# MRCS-4-Station-Tel-Control.net
KiCad netlist of a schematic drawn in EAGLE
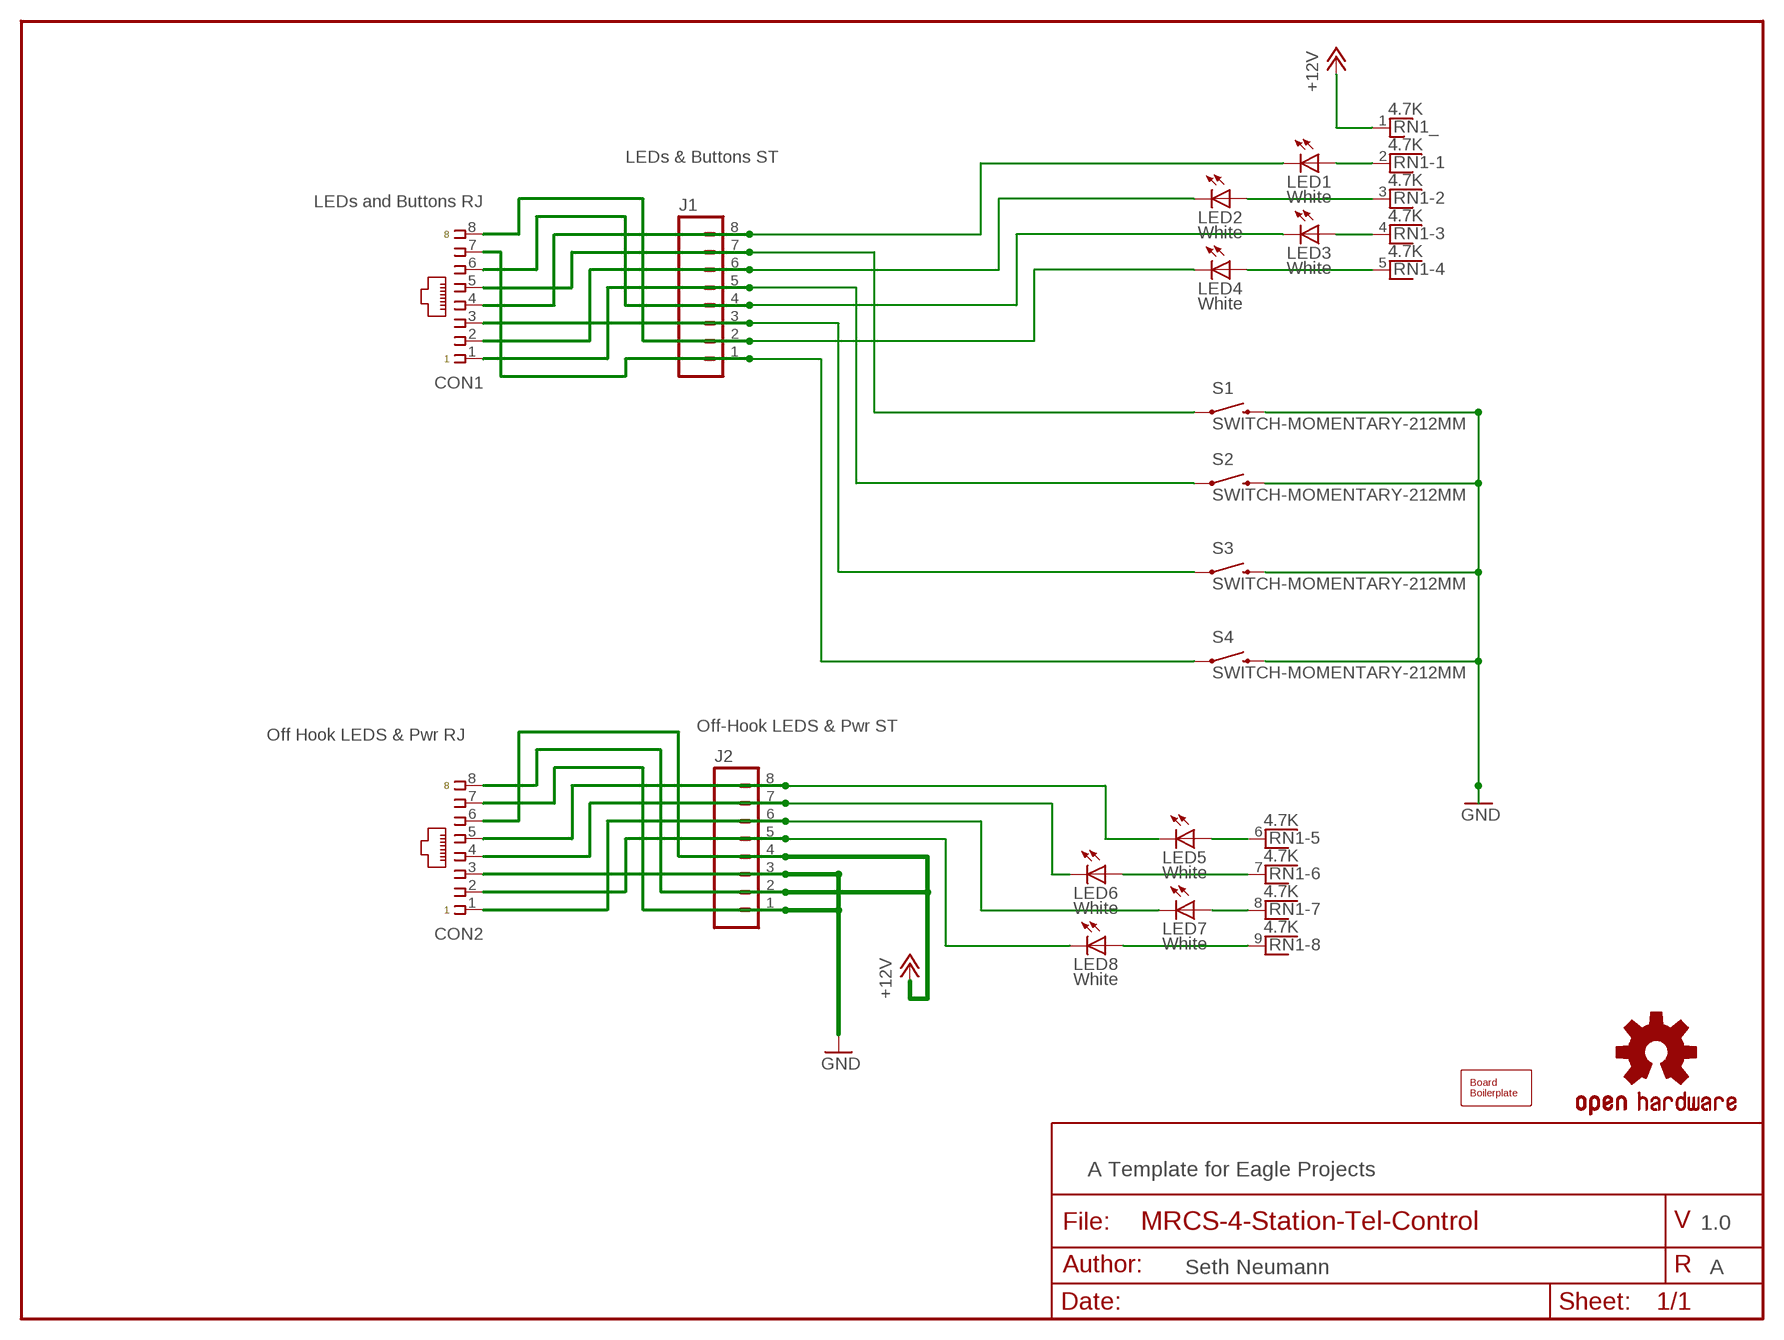
[diagram p0: schematic, sheet 1]

(export (version "E")
  (design (tool "Eeschema 10.0.6"))
  (components
    (comp (ref "BOARD1")
      (value "BOARD80X100")
      (footprint "eagle-import:BOARD-DINRAIL-3.17INX10CM")
      (libsource (lib "eagle-import") (part "BOARD80X100"))
    )
    (comp (ref "CON1")
      (value "LEDs and Buttons RJ")
      (footprint "eagle-import:RJ45-NO-SHIELD")
      (libsource (lib "eagle-import") (part "CONNECTOR-RJ45-FRONT"))
    )
    (comp (ref "CON2")
      (value "Off Hook LEDS & Pwr RJ")
      (footprint "eagle-import:RJ45-NO-SHIELD")
      (libsource (lib "eagle-import") (part "CONNECTOR-RJ45-FRONT"))
    )
    (comp (ref "J1")
      (value "LEDs & Buttons ST")
      (footprint "eagle-import:1X08_LOCK")
      (libsource (lib "eagle-import") (part "CONNECTOR-M08LOCK"))
    )
    (comp (ref "J2")
      (value "Off-Hook LEDS & Pwr ST")
      (footprint "eagle-import:1X08_LOCK")
      (libsource (lib "eagle-import") (part "CONNECTOR-M08LOCK"))
    )
    (comp (ref "LED1")
      (value "White")
      (footprint "eagle-import:LED5MM")
      (libsource (lib "eagle-import") (part "LEDLED5MM"))
    )
    (comp (ref "LED2")
      (value "White")
      (footprint "eagle-import:LED5MM")
      (libsource (lib "eagle-import") (part "LEDLED5MM"))
    )
    (comp (ref "LED3")
      (value "White")
      (footprint "eagle-import:LED5MM")
      (libsource (lib "eagle-import") (part "LEDLED5MM"))
    )
    (comp (ref "LED4")
      (value "White")
      (footprint "eagle-import:LED5MM")
      (libsource (lib "eagle-import") (part "LEDLED5MM"))
    )
    (comp (ref "LED5")
      (value "White")
      (footprint "eagle-import:LED5MM")
      (libsource (lib "eagle-import") (part "LEDLED5MM"))
    )
    (comp (ref "LED6")
      (value "White")
      (footprint "eagle-import:LED5MM")
      (libsource (lib "eagle-import") (part "LEDLED5MM"))
    )
    (comp (ref "LED7")
      (value "White")
      (footprint "eagle-import:LED5MM")
      (libsource (lib "eagle-import") (part "LEDLED5MM"))
    )
    (comp (ref "LED8")
      (value "White")
      (footprint "eagle-import:LED5MM")
      (libsource (lib "eagle-import") (part "LEDLED5MM"))
    )
    (comp (ref "OSHW1")
      (value "DOC-OSHW-LOGO-M")
      (footprint "eagle-import:OSHW-LOGO-M")
      (libsource (lib "eagle-import") (part "DOC-OSHW-LOGO-M"))
    )
    (comp (ref "RN1")
      (value "4.7K")
      (footprint "eagle-import:RN-9")
      (libsource (lib "eagle-import") (part "RNX8"))
    )
    (comp (ref "S1")
      (value "SWITCH-MOMENTARY-212MM")
      (footprint "eagle-import:TACTILE-PTH-12MM")
      (libsource (lib "eagle-import") (part "SWITCH-MOMENTARY-212MM"))
    )
    (comp (ref "S2")
      (value "SWITCH-MOMENTARY-212MM")
      (footprint "eagle-import:TACTILE-PTH-12MM")
      (libsource (lib "eagle-import") (part "SWITCH-MOMENTARY-212MM"))
    )
    (comp (ref "S3")
      (value "SWITCH-MOMENTARY-212MM")
      (footprint "eagle-import:TACTILE-PTH-12MM")
      (libsource (lib "eagle-import") (part "SWITCH-MOMENTARY-212MM"))
    )
    (comp (ref "S4")
      (value "SWITCH-MOMENTARY-212MM")
      (footprint "eagle-import:TACTILE-PTH-12MM")
      (libsource (lib "eagle-import") (part "SWITCH-MOMENTARY-212MM"))
    )
  )
  (nets
    (net (code "1") (name "+12V") (class "Default")
      (node (ref "CON2") (pin "6") (pinfunction "6_6") (pintype "passive"))
      (node (ref "CON2") (pin "8") (pinfunction "8_8") (pintype "passive"))
      (node (ref "J2") (pin "2") (pinfunction "2_2") (pintype "passive"))
      (node (ref "J2") (pin "4") (pinfunction "4_4") (pintype "passive"))
      (node (ref "RN1") (pin "1") (pinfunction "1_1") (pintype "passive"))
    )
    (net (code "2") (name "GND") (class "Default")
      (node (ref "CON2") (pin "3") (pinfunction "3_3") (pintype "passive"))
      (node (ref "CON2") (pin "7") (pinfunction "7_7") (pintype "passive"))
      (node (ref "J2") (pin "1") (pinfunction "1_1") (pintype "passive"))
      (node (ref "J2") (pin "3") (pinfunction "3_3") (pintype "passive"))
      (node (ref "S1") (pin "3") (pinfunction "2_3") (pintype "passive"))
      (node (ref "S2") (pin "3") (pinfunction "2_3") (pintype "passive"))
      (node (ref "S3") (pin "3") (pinfunction "2_3") (pintype "passive"))
      (node (ref "S4") (pin "3") (pinfunction "2_3") (pintype "passive"))
    )
    (net (code "3") (name "Net-(CON1-Pad1)") (class "Default")
      (node (ref "CON1") (pin "1") (pinfunction "1_1") (pintype "passive"))
      (node (ref "J1") (pin "5") (pinfunction "5_5") (pintype "passive"))
      (node (ref "S2") (pin "1") (pinfunction "1_1") (pintype "passive"))
    )
    (net (code "4") (name "Net-(CON1-Pad3)") (class "Default")
      (node (ref "CON1") (pin "3") (pinfunction "3_3") (pintype "passive"))
      (node (ref "J1") (pin "3") (pinfunction "3_3") (pintype "passive"))
      (node (ref "S3") (pin "1") (pinfunction "1_1") (pintype "passive"))
    )
    (net (code "5") (name "Net-(CON1-Pad5)") (class "Default")
      (node (ref "CON1") (pin "5") (pinfunction "5_5") (pintype "passive"))
      (node (ref "J1") (pin "7") (pinfunction "7_7") (pintype "passive"))
      (node (ref "S1") (pin "1") (pinfunction "1_1") (pintype "passive"))
    )
    (net (code "6") (name "Net-(CON1-Pad7)") (class "Default")
      (node (ref "CON1") (pin "7") (pinfunction "7_7") (pintype "passive"))
      (node (ref "J1") (pin "1") (pinfunction "1_1") (pintype "passive"))
      (node (ref "S4") (pin "1") (pinfunction "1_1") (pintype "passive"))
    )
    (net (code "7") (name "Net-(LED1-C)") (class "Default")
      (node (ref "CON1") (pin "4") (pinfunction "4_4") (pintype "passive"))
      (node (ref "J1") (pin "8") (pinfunction "8_8") (pintype "passive"))
      (node (ref "LED1") (pin "K") (pinfunction "C_K") (pintype "passive"))
    )
    (net (code "8") (name "Net-(LED2-C)") (class "Default")
      (node (ref "CON1") (pin "2") (pinfunction "2_2") (pintype "passive"))
      (node (ref "J1") (pin "6") (pinfunction "6_6") (pintype "passive"))
      (node (ref "LED2") (pin "K") (pinfunction "C_K") (pintype "passive"))
    )
    (net (code "9") (name "Net-(LED3-C)") (class "Default")
      (node (ref "CON1") (pin "6") (pinfunction "6_6") (pintype "passive"))
      (node (ref "J1") (pin "4") (pinfunction "4_4") (pintype "passive"))
      (node (ref "LED3") (pin "K") (pinfunction "C_K") (pintype "passive"))
    )
    (net (code "10") (name "Net-(LED4-C)") (class "Default")
      (node (ref "CON1") (pin "8") (pinfunction "8_8") (pintype "passive"))
      (node (ref "J1") (pin "2") (pinfunction "2_2") (pintype "passive"))
      (node (ref "LED4") (pin "K") (pinfunction "C_K") (pintype "passive"))
    )
    (net (code "11") (name "Net-(LED5-C)") (class "Default")
      (node (ref "CON2") (pin "5") (pinfunction "5_5") (pintype "passive"))
      (node (ref "J2") (pin "8") (pinfunction "8_8") (pintype "passive"))
      (node (ref "LED5") (pin "K") (pinfunction "C_K") (pintype "passive"))
    )
    (net (code "12") (name "Net-(LED6-C)") (class "Default")
      (node (ref "CON2") (pin "4") (pinfunction "4_4") (pintype "passive"))
      (node (ref "J2") (pin "7") (pinfunction "7_7") (pintype "passive"))
      (node (ref "LED6") (pin "K") (pinfunction "C_K") (pintype "passive"))
    )
    (net (code "13") (name "Net-(LED7-C)") (class "Default")
      (node (ref "CON2") (pin "1") (pinfunction "1_1") (pintype "passive"))
      (node (ref "J2") (pin "6") (pinfunction "6_6") (pintype "passive"))
      (node (ref "LED7") (pin "K") (pinfunction "C_K") (pintype "passive"))
    )
    (net (code "14") (name "Net-(LED8-C)") (class "Default")
      (node (ref "CON2") (pin "2") (pinfunction "2_2") (pintype "passive"))
      (node (ref "J2") (pin "5") (pinfunction "5_5") (pintype "passive"))
      (node (ref "LED8") (pin "K") (pinfunction "C_K") (pintype "passive"))
    )
    (net (code "15") (name "Net-(RN1A-1)") (class "Default")
      (node (ref "LED1") (pin "A") (pinfunction "A_A") (pintype "passive"))
      (node (ref "RN1") (pin "2") (pinfunction "1_2") (pintype "passive"))
    )
    (net (code "16") (name "Net-(RN1B-1)") (class "Default")
      (node (ref "LED2") (pin "A") (pinfunction "A_A") (pintype "passive"))
      (node (ref "RN1") (pin "3") (pinfunction "1_3") (pintype "passive"))
    )
    (net (code "17") (name "Net-(RN1C-1)") (class "Default")
      (node (ref "LED3") (pin "A") (pinfunction "A_A") (pintype "passive"))
      (node (ref "RN1") (pin "4") (pinfunction "1_4") (pintype "passive"))
    )
    (net (code "18") (name "Net-(RN1D-1)") (class "Default")
      (node (ref "LED4") (pin "A") (pinfunction "A_A") (pintype "passive"))
      (node (ref "RN1") (pin "5") (pinfunction "1_5") (pintype "passive"))
    )
    (net (code "19") (name "Net-(RN1E-1)") (class "Default")
      (node (ref "LED5") (pin "A") (pinfunction "A_A") (pintype "passive"))
      (node (ref "RN1") (pin "6") (pinfunction "1_6") (pintype "passive"))
    )
    (net (code "20") (name "Net-(RN1F-1)") (class "Default")
      (node (ref "LED6") (pin "A") (pinfunction "A_A") (pintype "passive"))
      (node (ref "RN1") (pin "7") (pinfunction "1_7") (pintype "passive"))
    )
    (net (code "21") (name "Net-(RN1G-1)") (class "Default")
      (node (ref "LED7") (pin "A") (pinfunction "A_A") (pintype "passive"))
      (node (ref "RN1") (pin "8") (pinfunction "1_8") (pintype "passive"))
    )
    (net (code "22") (name "Net-(RN1H-1)") (class "Default")
      (node (ref "LED8") (pin "A") (pinfunction "A_A") (pintype "passive"))
      (node (ref "RN1") (pin "9") (pinfunction "1_9") (pintype "passive"))
    )
  )
)
